# Model52.net
KiCad netlist of a schematic drawn in EAGLE
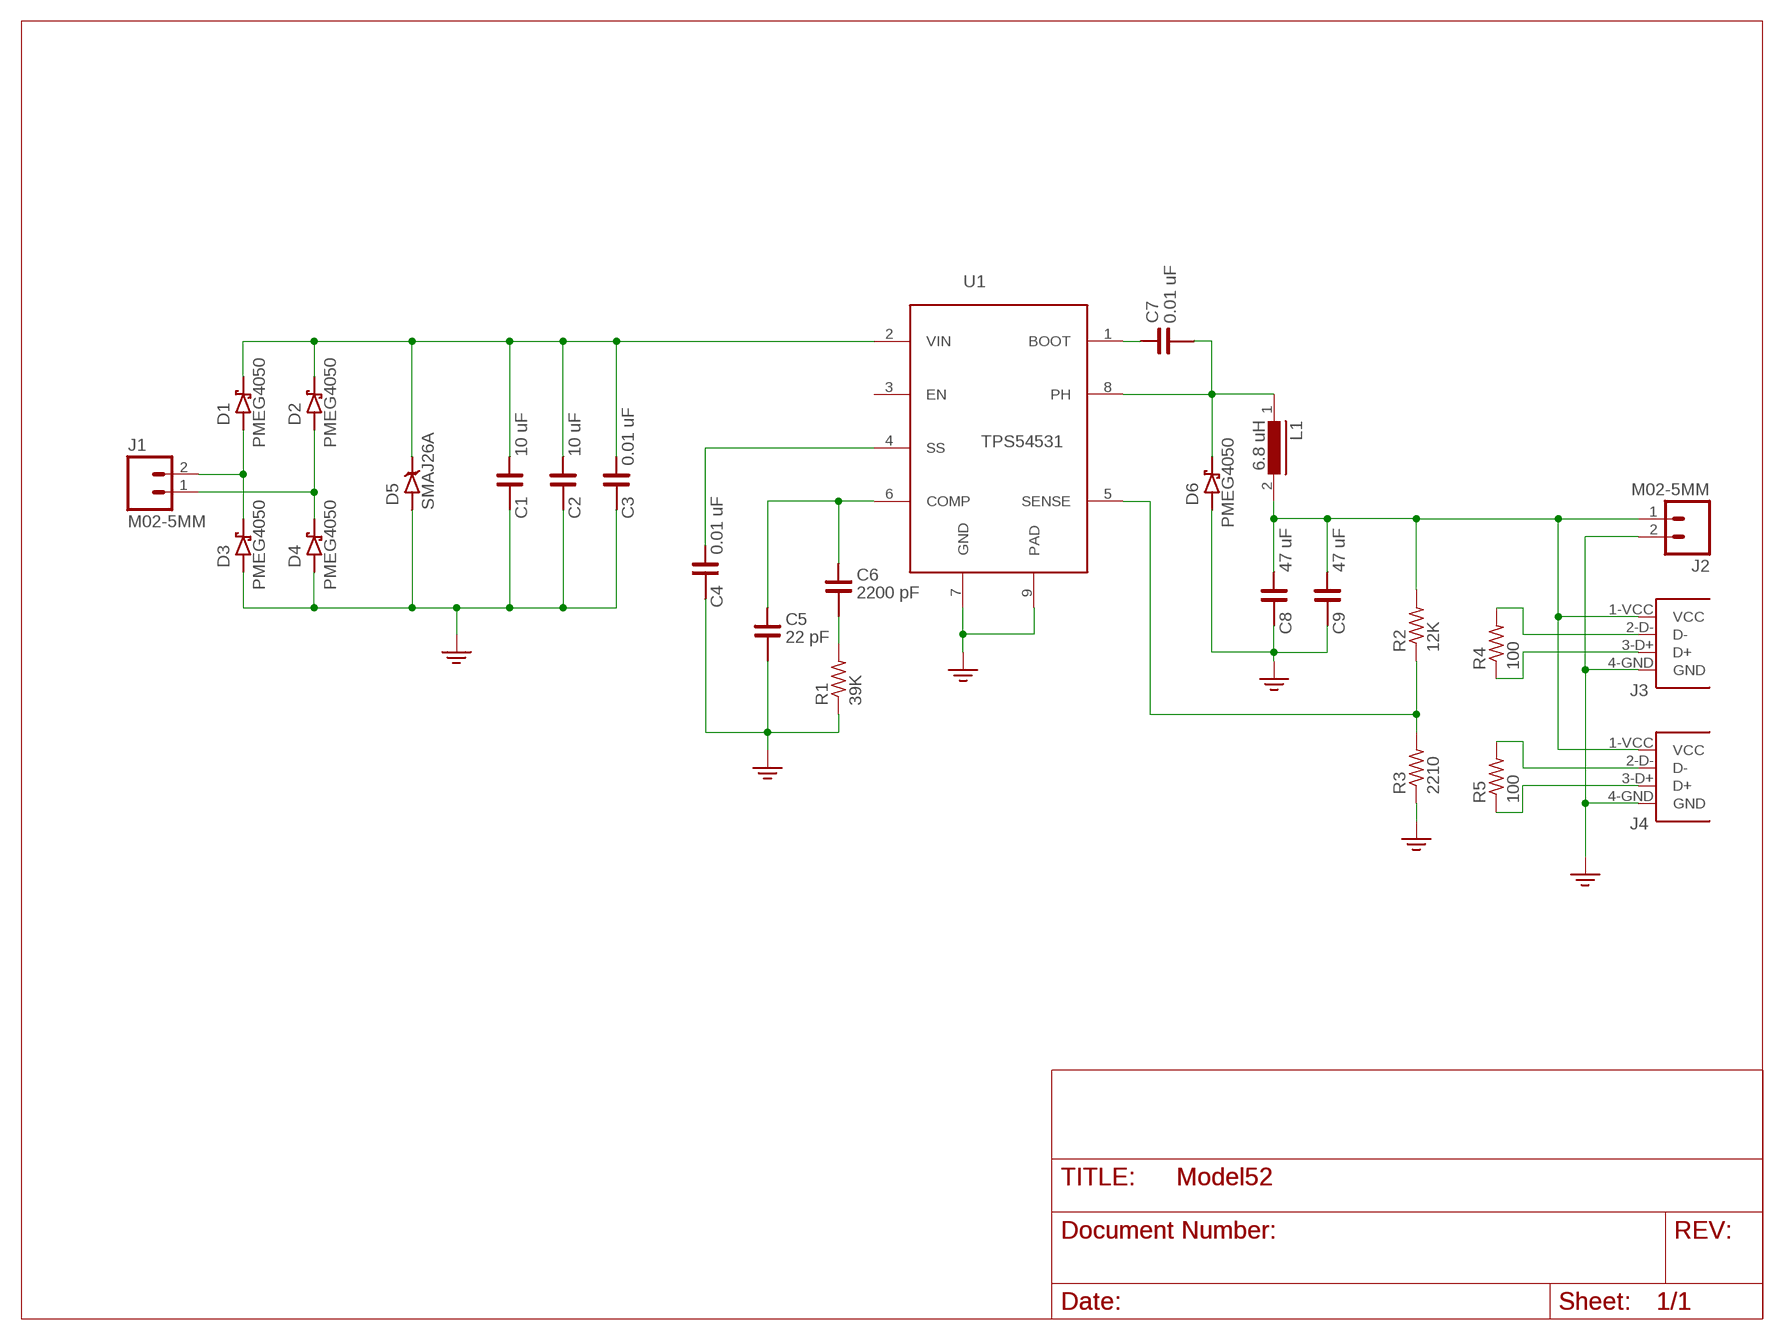
[diagram p0: schematic, sheet 1]

(export (version "E")
  (design (tool "Eeschema 10.0.6"))
  (components
    (comp (ref "C1")
      (value "10 uF")
      (footprint "eagle-import:1210")
      (libsource (lib "eagle-import") (part "CN-1210"))
    )
    (comp (ref "C2")
      (value "10 uF")
      (footprint "eagle-import:1210")
      (libsource (lib "eagle-import") (part "CN-1210"))
    )
    (comp (ref "C3")
      (value "0.01 uF")
      (footprint "eagle-import:0805")
      (libsource (lib "eagle-import") (part "CN-0805"))
    )
    (comp (ref "C4")
      (value "0.01 uF")
      (footprint "eagle-import:0805")
      (libsource (lib "eagle-import") (part "CN-0805"))
    )
    (comp (ref "C5")
      (value "22 pF")
      (footprint "eagle-import:0805")
      (libsource (lib "eagle-import") (part "CN-0805"))
    )
    (comp (ref "C6")
      (value "2200 pF")
      (footprint "eagle-import:0805")
      (libsource (lib "eagle-import") (part "CN-0805"))
    )
    (comp (ref "C7")
      (value "0.01 uF")
      (footprint "eagle-import:0805")
      (libsource (lib "eagle-import") (part "CN-0805"))
    )
    (comp (ref "C8")
      (value "47 uF")
      (footprint "eagle-import:C1206")
      (libsource (lib "eagle-import") (part "CN-1206"))
    )
    (comp (ref "C9")
      (value "47 uF")
      (footprint "eagle-import:C1206")
      (libsource (lib "eagle-import") (part "CN-1206"))
    )
    (comp (ref "D1")
      (value "PMEG4050EP")
      (footprint "eagle-import:SOD128")
      (libsource (lib "eagle-import") (part "PMEG4050EP"))
    )
    (comp (ref "D2")
      (value "PMEG4050EP")
      (footprint "eagle-import:SOD128")
      (libsource (lib "eagle-import") (part "PMEG4050EP"))
    )
    (comp (ref "D3")
      (value "PMEG4050EP")
      (footprint "eagle-import:SOD128")
      (libsource (lib "eagle-import") (part "PMEG4050EP"))
    )
    (comp (ref "D4")
      (value "PMEG4050EP")
      (footprint "eagle-import:SOD128")
      (libsource (lib "eagle-import") (part "PMEG4050EP"))
    )
    (comp (ref "D5")
      (value "SMAJ26A")
      (footprint "eagle-import:DO214BA")
      (libsource (lib "eagle-import") (part "SMAJ26A"))
    )
    (comp (ref "D6")
      (value "PMEG4050EP")
      (footprint "eagle-import:SOD128")
      (libsource (lib "eagle-import") (part "PMEG4050EP"))
    )
    (comp (ref "J1")
      (value "M02-5MM")
      (footprint "eagle-import:SCREWTERMINAL-5MM-2")
      (libsource (lib "eagle-import") (part "M02-5MM"))
    )
    (comp (ref "J2")
      (value "M02-5MM")
      (footprint "eagle-import:SCREWTERMINAL-5MM-2")
      (libsource (lib "eagle-import") (part "M02-5MM"))
    )
    (comp (ref "J3")
      (value "87520-USB-A-FEMALE")
      (footprint "eagle-import:87520-USB-A-FEMALE")
      (libsource (lib "eagle-import") (part "87520-USB-A-FEMALE"))
    )
    (comp (ref "J4")
      (value "87520-USB-A-FEMALE")
      (footprint "eagle-import:87520-USB-A-FEMALE")
      (libsource (lib "eagle-import") (part "87520-USB-A-FEMALE"))
    )
    (comp (ref "L1")
      (value "6.8 uH")
      (footprint "eagle-import:DR125")
      (libsource (lib "eagle-import") (part "DR125"))
    )
    (comp (ref "R1")
      (value "39K")
      (footprint "eagle-import:R0805")
      (libsource (lib "eagle-import") (part "R-US_R0805"))
    )
    (comp (ref "R2")
      (value "12K")
      (footprint "eagle-import:R0805")
      (libsource (lib "eagle-import") (part "R-US_R0805"))
    )
    (comp (ref "R3")
      (value "2210")
      (footprint "eagle-import:R0805")
      (libsource (lib "eagle-import") (part "R-US_R0805"))
    )
    (comp (ref "R4")
      (value "100")
      (footprint "eagle-import:R0805")
      (libsource (lib "eagle-import") (part "R-US_R0805"))
    )
    (comp (ref "R5")
      (value "100")
      (footprint "eagle-import:R0805")
      (libsource (lib "eagle-import") (part "R-US_R0805"))
    )
    (comp (ref "U1")
      (value "TPS54531")
      (footprint "eagle-import:SOIC127P600X170-9N")
      (libsource (lib "eagle-import") (part "TPS54531"))
    )
  )
  (nets
    (net (code "1") (name "GND") (class "Default")
      (node (ref "C1") (pin "2") (pinfunction "P$2_2") (pintype "bidirectional"))
      (node (ref "C2") (pin "2") (pinfunction "P$2_2") (pintype "bidirectional"))
      (node (ref "C3") (pin "2") (pinfunction "P$2_2") (pintype "bidirectional"))
      (node (ref "C4") (pin "2") (pinfunction "P$2_2") (pintype "bidirectional"))
      (node (ref "C5") (pin "2") (pinfunction "P$2_2") (pintype "bidirectional"))
      (node (ref "C8") (pin "2") (pinfunction "P$2_2") (pintype "bidirectional"))
      (node (ref "C9") (pin "2") (pinfunction "P$2_2") (pintype "bidirectional"))
      (node (ref "D3") (pin "P$1A") (pinfunction "P$1A_P$1A") (pintype "input"))
      (node (ref "D4") (pin "P$1A") (pinfunction "P$1A_P$1A") (pintype "input"))
      (node (ref "D5") (pin "A") (pinfunction "P$1A_A") (pintype "input"))
      (node (ref "D6") (pin "P$1A") (pinfunction "P$1A_P$1A") (pintype "input"))
      (node (ref "J2") (pin "2") (pinfunction "2_2") (pintype "passive"))
      (node (ref "J3") (pin "4-GND") (pinfunction "GND_4-GND") (pintype "power_in"))
      (node (ref "J4") (pin "4-GND") (pinfunction "GND_4-GND") (pintype "power_in"))
      (node (ref "R1") (pin "1") (pinfunction "1_1") (pintype "passive"))
      (node (ref "R3") (pin "1") (pinfunction "1_1") (pintype "passive"))
      (node (ref "U1") (pin "7") (pinfunction "GND_7") (pintype "power_in"))
      (node (ref "U1") (pin "9") (pinfunction "PAD_9") (pintype "power_in"))
    )
    (net (code "2") (name "Net-(C1-P$1)") (class "Default")
      (node (ref "C1") (pin "1") (pinfunction "P$1_1") (pintype "bidirectional"))
      (node (ref "C2") (pin "1") (pinfunction "P$1_1") (pintype "bidirectional"))
      (node (ref "C3") (pin "1") (pinfunction "P$1_1") (pintype "bidirectional"))
      (node (ref "D1") (pin "P$2C") (pinfunction "P$2C_P$2C") (pintype "output"))
      (node (ref "D2") (pin "P$2C") (pinfunction "P$2C_P$2C") (pintype "output"))
      (node (ref "D5") (pin "C") (pinfunction "P$2C_C") (pintype "output"))
      (node (ref "U1") (pin "2") (pinfunction "VIN_2") (pintype "power_in"))
    )
    (net (code "3") (name "Net-(C4-P$1)") (class "Default")
      (node (ref "C4") (pin "1") (pinfunction "P$1_1") (pintype "bidirectional"))
      (node (ref "U1") (pin "4") (pinfunction "SS_4") (pintype "bidirectional"))
    )
    (net (code "4") (name "Net-(C5-P$1)") (class "Default")
      (node (ref "C5") (pin "1") (pinfunction "P$1_1") (pintype "bidirectional"))
      (node (ref "C6") (pin "1") (pinfunction "P$1_1") (pintype "bidirectional"))
      (node (ref "U1") (pin "6") (pinfunction "COMP_6") (pintype "bidirectional"))
    )
    (net (code "5") (name "Net-(C6-P$2)") (class "Default")
      (node (ref "C6") (pin "2") (pinfunction "P$2_2") (pintype "bidirectional"))
      (node (ref "R1") (pin "2") (pinfunction "2_2") (pintype "passive"))
    )
    (net (code "6") (name "Net-(C7-P$1)") (class "Default")
      (node (ref "C7") (pin "1") (pinfunction "P$1_1") (pintype "bidirectional"))
      (node (ref "U1") (pin "1") (pinfunction "BOOT_1") (pintype "input"))
    )
    (net (code "7") (name "Net-(C7-P$2)") (class "Default")
      (node (ref "C7") (pin "2") (pinfunction "P$2_2") (pintype "bidirectional"))
      (node (ref "D6") (pin "P$2C") (pinfunction "P$2C_P$2C") (pintype "output"))
      (node (ref "L1") (pin "1") (pinfunction "1_1") (pintype "passive"))
      (node (ref "U1") (pin "8") (pinfunction "PH_8") (pintype "power_in"))
    )
    (net (code "8") (name "Net-(C8-P$1)") (class "Default")
      (node (ref "C8") (pin "1") (pinfunction "P$1_1") (pintype "bidirectional"))
      (node (ref "C9") (pin "1") (pinfunction "P$1_1") (pintype "bidirectional"))
      (node (ref "J2") (pin "1") (pinfunction "1_1") (pintype "passive"))
      (node (ref "J3") (pin "1-VCC") (pinfunction "VCC_1-VCC") (pintype "power_in"))
      (node (ref "J4") (pin "1-VCC") (pinfunction "VCC_1-VCC") (pintype "power_in"))
      (node (ref "L1") (pin "2") (pinfunction "2_2") (pintype "passive"))
      (node (ref "R2") (pin "2") (pinfunction "2_2") (pintype "passive"))
    )
    (net (code "9") (name "Net-(D1-PadP$1A)") (class "Default")
      (node (ref "D1") (pin "P$1A") (pinfunction "P$1A_P$1A") (pintype "input"))
      (node (ref "D3") (pin "P$2C") (pinfunction "P$2C_P$2C") (pintype "output"))
      (node (ref "J1") (pin "2") (pinfunction "2_2") (pintype "passive"))
    )
    (net (code "10") (name "Net-(D2-PadP$1A)") (class "Default")
      (node (ref "D2") (pin "P$1A") (pinfunction "P$1A_P$1A") (pintype "input"))
      (node (ref "D4") (pin "P$2C") (pinfunction "P$2C_P$2C") (pintype "output"))
      (node (ref "J1") (pin "1") (pinfunction "1_1") (pintype "passive"))
    )
    (net (code "11") (name "Net-(J3-D+)") (class "Default")
      (node (ref "J3") (pin "3-D+") (pinfunction "D+_3-D+") (pintype "bidirectional"))
      (node (ref "R4") (pin "1") (pinfunction "1_1") (pintype "passive"))
    )
    (net (code "12") (name "Net-(J3-D-)") (class "Default")
      (node (ref "J3") (pin "2-D-") (pinfunction "D-_2-D-") (pintype "bidirectional"))
      (node (ref "R4") (pin "2") (pinfunction "2_2") (pintype "passive"))
    )
    (net (code "13") (name "Net-(J4-D+)") (class "Default")
      (node (ref "J4") (pin "3-D+") (pinfunction "D+_3-D+") (pintype "bidirectional"))
      (node (ref "R5") (pin "1") (pinfunction "1_1") (pintype "passive"))
    )
    (net (code "14") (name "Net-(J4-D-)") (class "Default")
      (node (ref "J4") (pin "2-D-") (pinfunction "D-_2-D-") (pintype "bidirectional"))
      (node (ref "R5") (pin "2") (pinfunction "2_2") (pintype "passive"))
    )
    (net (code "15") (name "Net-(U1-SENSE)") (class "Default")
      (node (ref "R2") (pin "1") (pinfunction "1_1") (pintype "passive"))
      (node (ref "R3") (pin "2") (pinfunction "2_2") (pintype "passive"))
      (node (ref "U1") (pin "5") (pinfunction "SENSE_5") (pintype "bidirectional"))
    )
    (net (code "16") (name "unconnected-(U1-EN-Pad3)") (class "Default")
      (node (ref "U1") (pin "3") (pinfunction "EN_3") (pintype "input"))
    )
  )
)
